# core.net
KiCad netlist of a schematic drawn in Altium Designer
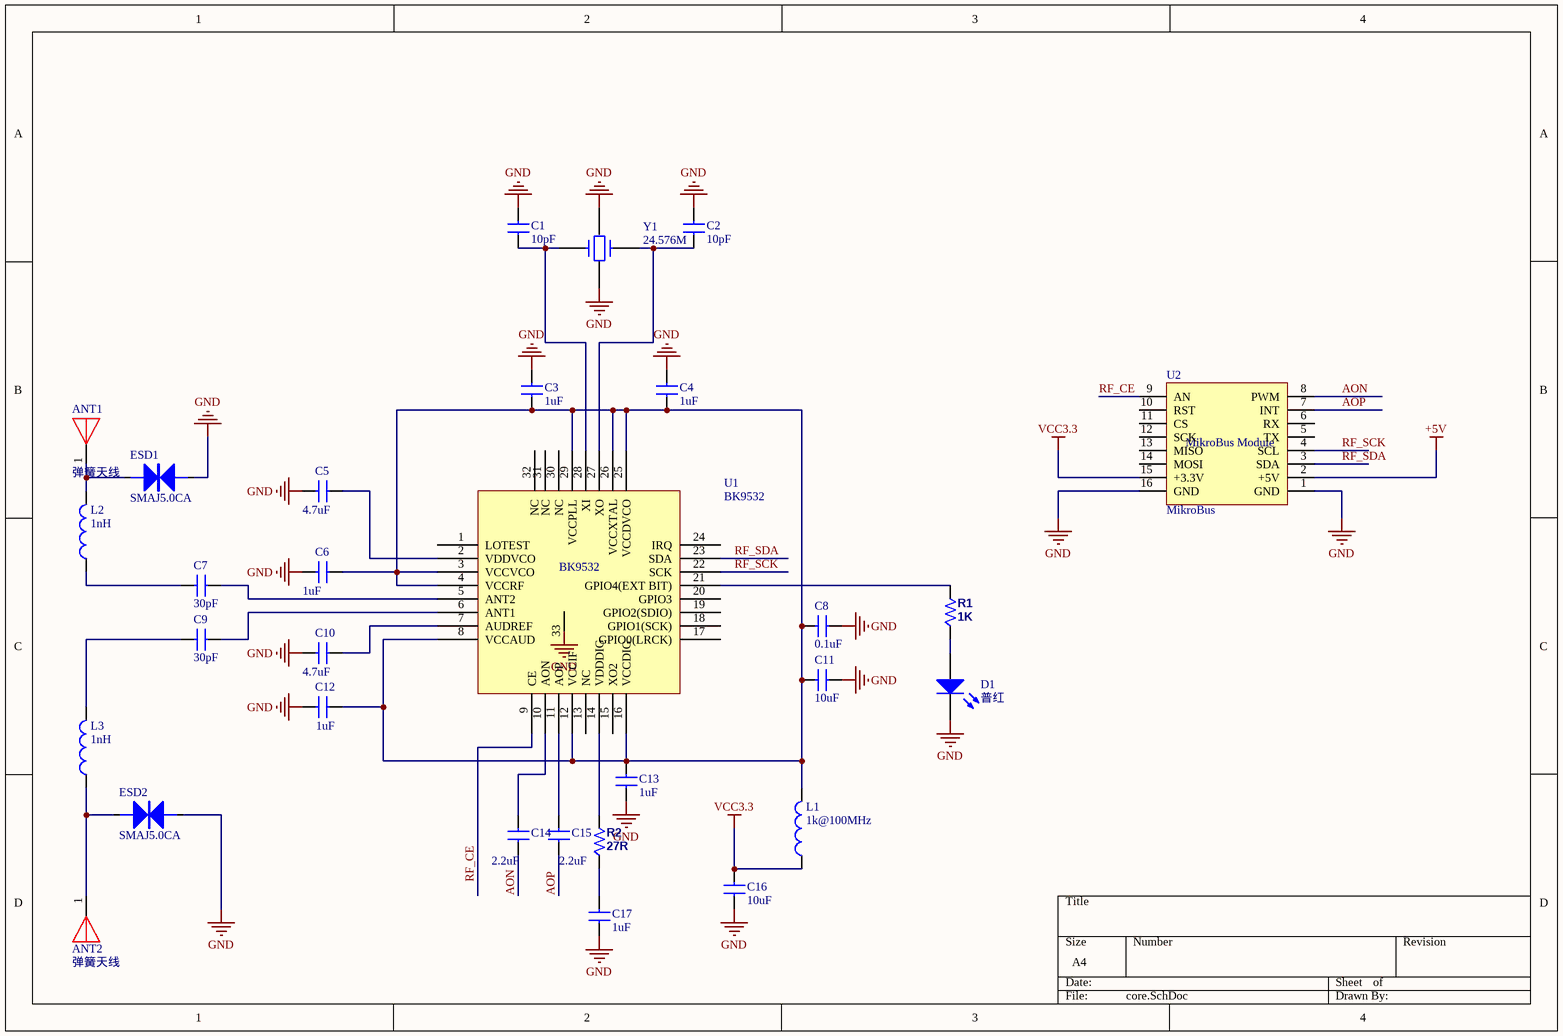
[diagram p0: core.SchDoc]

(export (version "E")
  (design (tool "Eeschema 10.0.6"))
  (components
    (comp (ref "ANT1")
      (value "弹簧天线")
      (footprint "ANT")
      (description "ANT")
      (libsource (lib "二极管") (part "ANT"))
    )
    (comp (ref "ANT2")
      (value "弹簧天线")
      (footprint "ANT")
      (description "ANT")
      (libsource (lib "二极管") (part "ANT"))
    )
    (comp (ref "C1")
      (value "10pF")
      (footprint "C0603")
      (description "0603-10pF/50V 贴片层叠电容")
      (libsource (lib "兰格封装") (part "CAP 0603-10pF/50V"))
    )
    (comp (ref "C2")
      (value "10pF")
      (footprint "C0603")
      (description "0603-10pF/50V 贴片层叠电容")
      (libsource (lib "兰格封装") (part "CAP 0603-10pF/50V"))
    )
    (comp (ref "C3")
      (value "1uF")
      (footprint "C0603")
      (description "0805-68pF/50V-J5%贴片层叠电容")
      (libsource (lib "兰格封装") (part "CAP 0805-68pF/50V"))
    )
    (comp (ref "C4")
      (value "1uF")
      (footprint "C0603")
      (description "0805-68pF/50V-J5%贴片层叠电容")
      (libsource (lib "兰格封装") (part "CAP 0805-68pF/50V"))
    )
    (comp (ref "C5")
      (value "4.7uF")
      (footprint "C0603")
      (description "0805-68pF/50V-J5%贴片层叠电容")
      (libsource (lib "兰格封装") (part "CAP 0805-68pF/50V"))
    )
    (comp (ref "C6")
      (value "1uF")
      (footprint "C0603")
      (description "0805-68pF/50V-J5%贴片层叠电容")
      (libsource (lib "兰格封装") (part "CAP 0805-68pF/50V"))
    )
    (comp (ref "C7")
      (value "30pF")
      (footprint "C0603")
      (description "0603-33pF/50V   贴片层叠电容")
      (libsource (lib "兰格封装") (part "CAP 0603-33pF/50V"))
    )
    (comp (ref "C8")
      (value "0.1uF")
      (footprint "C0603")
      (description "0805-68pF/50V-J5%贴片层叠电容")
      (libsource (lib "兰格封装") (part "CAP 0805-68pF/50V"))
    )
    (comp (ref "C9")
      (value "30pF")
      (footprint "C0603")
      (description "0603-33pF/50V   贴片层叠电容")
      (libsource (lib "兰格封装") (part "CAP 0603-33pF/50V"))
    )
    (comp (ref "C10")
      (value "4.7uF")
      (footprint "C0603")
      (description "0805-68pF/50V-J5%贴片层叠电容")
      (libsource (lib "兰格封装") (part "CAP 0805-68pF/50V"))
    )
    (comp (ref "C11")
      (value "10uF")
      (footprint "C0603")
      (description "0805-68pF/50V-J5%贴片层叠电容")
      (libsource (lib "兰格封装") (part "CAP 0805-68pF/50V"))
    )
    (comp (ref "C12")
      (value "1uF")
      (footprint "C0603")
      (description "0805-68pF/50V-J5%贴片层叠电容")
      (libsource (lib "兰格封装") (part "CAP 0805-68pF/50V"))
    )
    (comp (ref "C13")
      (value "1uF")
      (footprint "C0603")
      (description "0805-68pF/50V-J5%贴片层叠电容")
      (libsource (lib "兰格封装") (part "CAP 0805-68pF/50V"))
    )
    (comp (ref "C14")
      (value "2.2uF")
      (footprint "C0603")
      (description "0805-68pF/50V-J5%贴片层叠电容")
      (libsource (lib "兰格封装") (part "CAP 0805-68pF/50V"))
    )
    (comp (ref "C15")
      (value "2.2uF")
      (footprint "C0603")
      (description "0805-68pF/50V-J5%贴片层叠电容")
      (libsource (lib "兰格封装") (part "CAP 0805-68pF/50V"))
    )
    (comp (ref "C16")
      (value "10uF")
      (footprint "C0603")
      (description "0805-68pF/50V-J5%贴片层叠电容")
      (libsource (lib "兰格封装") (part "CAP 0805-68pF/50V"))
    )
    (comp (ref "C17")
      (value "1uF")
      (footprint "C0603")
      (description "0805-68pF/50V-J5%贴片层叠电容")
      (libsource (lib "兰格封装") (part "CAP 0805-68pF/50V"))
    )
    (comp (ref "D1")
      (value "普红")
      (footprint "LED 0805")
      (description "0805普亮贴片红灯")
      (libsource (lib "兰格封装") (part "LED  0805普亮贴片红灯"))
    )
    (comp (ref "ESD1")
      (value "SMAJ5.0CA")
      (footprint "SMAJ")
      (description "ESD 二极管")
      (libsource (lib "二极管") (part "ESD 防浪涌二极管"))
    )
    (comp (ref "ESD2")
      (value "SMAJ5.0CA")
      (footprint "SMAJ")
      (description "ESD 二极管")
      (libsource (lib "二极管") (part "ESD 防浪涌二极管"))
    )
    (comp (ref "L1")
      (value "1k@100MHz")
      (footprint "L0603")
      (description "磁珠")
      (libsource (lib "兰格封装") (part "电感  贴片  33UH"))
    )
    (comp (ref "L2")
      (value "1nH")
      (footprint "L0603")
      (description "0603 600R瓷珠电感")
      (libsource (lib "兰格封装") (part "电感  0603  600R"))
    )
    (comp (ref "L3")
      (value "1nH")
      (footprint "L0603")
      (description "0603 600R瓷珠电感")
      (libsource (lib "兰格封装") (part "电感  0603  600R"))
    )
    (comp (ref "R1")
      (value "1K")
      (footprint "R0603")
      (description "1206  K  5%  HS  贴片电阻")
      (libsource (lib "兰格封装") (part "RES1"))
    )
    (comp (ref "R2")
      (value "27R")
      (footprint "R0603")
      (description "1206  K  5%  HS  贴片电阻")
      (libsource (lib "兰格封装") (part "RES1"))
    )
    (comp (ref "U1")
      (value "BK9532")
      (footprint "QFN32")
      (description "QFN5x5 32")
      (libsource (lib "集成IC") (part "BK9532"))
    )
    (comp (ref "U2") (value "MikroBus") (footprint "MikroBus") (libsource (lib "集成IC") (part "MikroBus")))
    (comp (ref "Y1")
      (value "24.576M")
      (footprint "晶振   有源2520")
      (description "（未入库）24.576MHz  2520")
      (libsource (lib "晶体") (part "晶振  24.576MHz  49SMD"))
    )
  )
  (nets
    (net (code "1") (name "+5V") (class "Default")
      (node (ref "U2") (pin "2") (pinfunction "+5V_2") (pintype "passive"))
    )
    (net (code "2") (name "/AON") (class "Default")
      (node (ref "C14") (pin "1") (pinfunction "1_1") (pintype "passive"))
      (node (ref "U2") (pin "8") (pinfunction "PWM_8") (pintype "passive"))
    )
    (net (code "3") (name "/AOP") (class "Default")
      (node (ref "C15") (pin "1") (pinfunction "1_1") (pintype "passive"))
      (node (ref "U2") (pin "7") (pinfunction "INT_7") (pintype "passive"))
    )
    (net (code "4") (name "/RF_CE") (class "Default")
      (node (ref "U1") (pin "9") (pinfunction "CE_9") (pintype "passive"))
      (node (ref "U2") (pin "9") (pinfunction "AN_9") (pintype "passive"))
    )
    (net (code "5") (name "/RF_SCK") (class "Default")
      (node (ref "U1") (pin "22") (pinfunction "SCK_22") (pintype "passive"))
      (node (ref "U2") (pin "4") (pinfunction "SCL_4") (pintype "passive"))
    )
    (net (code "6") (name "/RF_SDA") (class "Default")
      (node (ref "U1") (pin "23") (pinfunction "SDA_23") (pintype "passive"))
      (node (ref "U2") (pin "3") (pinfunction "SDA_3") (pintype "passive"))
    )
    (net (code "7") (name "GND") (class "Default")
      (node (ref "C1") (pin "1") (pinfunction "1_1") (pintype "passive"))
      (node (ref "C10") (pin "1") (pinfunction "1_1") (pintype "passive"))
      (node (ref "C11") (pin "1") (pinfunction "1_1") (pintype "passive"))
      (node (ref "C12") (pin "1") (pinfunction "1_1") (pintype "passive"))
      (node (ref "C13") (pin "1") (pinfunction "1_1") (pintype "passive"))
      (node (ref "C16") (pin "1") (pinfunction "1_1") (pintype "passive"))
      (node (ref "C17") (pin "1") (pinfunction "1_1") (pintype "passive"))
      (node (ref "C2") (pin "1") (pinfunction "1_1") (pintype "passive"))
      (node (ref "C3") (pin "2") (pinfunction "2_2") (pintype "passive"))
      (node (ref "C4") (pin "2") (pinfunction "2_2") (pintype "passive"))
      (node (ref "C5") (pin "1") (pinfunction "1_1") (pintype "passive"))
      (node (ref "C6") (pin "1") (pinfunction "1_1") (pintype "passive"))
      (node (ref "C8") (pin "1") (pinfunction "1_1") (pintype "passive"))
      (node (ref "D1") (pin "2") (pinfunction "K_2") (pintype "passive"))
      (node (ref "ESD1") (pin "2") (pinfunction "2_2") (pintype "passive"))
      (node (ref "ESD2") (pin "1") (pinfunction "1_1") (pintype "passive"))
      (node (ref "U1") (pin "33") (pintype "passive"))
      (node (ref "U2") (pin "1") (pinfunction "GND_1") (pintype "passive"))
      (node (ref "U2") (pin "16") (pinfunction "GND_16") (pintype "passive"))
      (node (ref "Y1") (pin "2") (pinfunction "2_2") (pintype "passive"))
      (node (ref "Y1") (pin "4") (pinfunction "4_4") (pintype "passive"))
    )
    (net (code "8") (name "Net-(ANT1-Pad1)") (class "Default")
      (node (ref "ANT1") (pin "1") (pinfunction "1_1") (pintype "passive"))
      (node (ref "ESD1") (pin "1") (pinfunction "1_1") (pintype "passive"))
      (node (ref "L2") (pin "2") (pinfunction "2_2") (pintype "passive"))
    )
    (net (code "9") (name "Net-(ANT2-Pad1)") (class "Default")
      (node (ref "ANT2") (pin "1") (pinfunction "1_1") (pintype "passive"))
      (node (ref "ESD2") (pin "2") (pinfunction "2_2") (pintype "passive"))
      (node (ref "L3") (pin "1") (pinfunction "1_1") (pintype "passive"))
    )
    (net (code "10") (name "Net-(C7-Pad1)") (class "Default")
      (node (ref "C7") (pin "1") (pinfunction "1_1") (pintype "passive"))
      (node (ref "L2") (pin "1") (pinfunction "1_1") (pintype "passive"))
    )
    (net (code "11") (name "Net-(C9-Pad1)") (class "Default")
      (node (ref "C9") (pin "1") (pinfunction "1_1") (pintype "passive"))
      (node (ref "L3") (pin "2") (pinfunction "2_2") (pintype "passive"))
    )
    (net (code "12") (name "Net-(C17-Pad2)") (class "Default")
      (node (ref "C17") (pin "2") (pinfunction "2_2") (pintype "passive"))
      (node (ref "R2") (pin "1") (pintype "passive"))
    )
    (net (code "13") (name "Net-(D1-A)") (class "Default")
      (node (ref "D1") (pin "1") (pinfunction "A_1") (pintype "passive"))
      (node (ref "R1") (pin "1") (pintype "passive"))
    )
    (net (code "14") (name "Net-(U1-ANT1)") (class "Default")
      (node (ref "C9") (pin "2") (pinfunction "2_2") (pintype "passive"))
      (node (ref "U1") (pin "6") (pinfunction "ANT1_6") (pintype "passive"))
    )
    (net (code "15") (name "Net-(U1-ANT2)") (class "Default")
      (node (ref "C7") (pin "2") (pinfunction "2_2") (pintype "passive"))
      (node (ref "U1") (pin "5") (pinfunction "ANT2_5") (pintype "passive"))
    )
    (net (code "16") (name "Net-(U1-AON)") (class "Default")
      (node (ref "C14") (pin "2") (pinfunction "2_2") (pintype "passive"))
      (node (ref "U1") (pin "10") (pinfunction "AON_10") (pintype "passive"))
    )
    (net (code "17") (name "Net-(U1-AOP)") (class "Default")
      (node (ref "C15") (pin "2") (pinfunction "2_2") (pintype "passive"))
      (node (ref "U1") (pin "11") (pinfunction "AOP_11") (pintype "passive"))
    )
    (net (code "18") (name "Net-(U1-AUDREF)") (class "Default")
      (node (ref "C10") (pin "2") (pinfunction "2_2") (pintype "passive"))
      (node (ref "U1") (pin "7") (pinfunction "AUDREF_7") (pintype "passive"))
    )
    (net (code "19") (name "Net-(U1-GPIO4(EXT_BIT))") (class "Default")
      (node (ref "R1") (pin "2") (pintype "passive"))
      (node (ref "U1") (pin "21") (pinfunction "GPIO4(EXT_BIT)_21") (pintype "passive"))
    )
    (net (code "20") (name "Net-(U1-VCCAUD)") (class "Default")
      (node (ref "C11") (pin "2") (pinfunction "2_2") (pintype "passive"))
      (node (ref "C12") (pin "2") (pinfunction "2_2") (pintype "passive"))
      (node (ref "C13") (pin "2") (pinfunction "2_2") (pintype "passive"))
      (node (ref "C3") (pin "1") (pinfunction "1_1") (pintype "passive"))
      (node (ref "C4") (pin "1") (pinfunction "1_1") (pintype "passive"))
      (node (ref "C6") (pin "2") (pinfunction "2_2") (pintype "passive"))
      (node (ref "C8") (pin "2") (pinfunction "2_2") (pintype "passive"))
      (node (ref "L1") (pin "2") (pinfunction "2_2") (pintype "passive"))
      (node (ref "U1") (pin "12") (pinfunction "VCCIF_12") (pintype "passive"))
      (node (ref "U1") (pin "16") (pinfunction "VCCDIG_16") (pintype "passive"))
      (node (ref "U1") (pin "25") (pinfunction "VCCDVCO_25") (pintype "passive"))
      (node (ref "U1") (pin "26") (pinfunction "VCCXTAL_26") (pintype "passive"))
      (node (ref "U1") (pin "29") (pinfunction "VCCPLL_29") (pintype "passive"))
      (node (ref "U1") (pin "3") (pinfunction "VCCVCO_3") (pintype "passive"))
      (node (ref "U1") (pin "4") (pinfunction "VCCRF_4") (pintype "passive"))
      (node (ref "U1") (pin "8") (pinfunction "VCCAUD_8") (pintype "passive"))
    )
    (net (code "21") (name "Net-(U1-VDDDIG)") (class "Default")
      (node (ref "R2") (pin "2") (pintype "passive"))
      (node (ref "U1") (pin "14") (pinfunction "VDDDIG_14") (pintype "passive"))
    )
    (net (code "22") (name "Net-(U1-VDDVCO)") (class "Default")
      (node (ref "C5") (pin "2") (pinfunction "2_2") (pintype "passive"))
      (node (ref "U1") (pin "2") (pinfunction "VDDVCO_2") (pintype "passive"))
    )
    (net (code "23") (name "Net-(U1-XI)") (class "Default")
      (node (ref "C1") (pin "2") (pinfunction "2_2") (pintype "passive"))
      (node (ref "U1") (pin "28") (pinfunction "XI_28") (pintype "passive"))
      (node (ref "Y1") (pin "1") (pinfunction "1_1") (pintype "passive"))
    )
    (net (code "24") (name "Net-(U1-XO)") (class "Default")
      (node (ref "C2") (pin "2") (pinfunction "2_2") (pintype "passive"))
      (node (ref "U1") (pin "27") (pinfunction "XO_27") (pintype "passive"))
      (node (ref "Y1") (pin "3") (pinfunction "3_3") (pintype "passive"))
    )
    (net (code "25") (name "VCC3.3") (class "Default")
      (node (ref "C16") (pin "2") (pinfunction "2_2") (pintype "passive"))
      (node (ref "L1") (pin "1") (pinfunction "1_1") (pintype "passive"))
      (node (ref "U2") (pin "15") (pinfunction "+3.3V_15") (pintype "passive"))
    )
    (net (code "26") (name "unconnected-(U1-GPIO0(LRCK)-Pad17)") (class "Default")
      (node (ref "U1") (pin "17") (pinfunction "GPIO0(LRCK)_17") (pintype "passive"))
    )
    (net (code "27") (name "unconnected-(U1-GPIO1(SCK)-Pad18)") (class "Default")
      (node (ref "U1") (pin "18") (pinfunction "GPIO1(SCK)_18") (pintype "passive"))
    )
    (net (code "28") (name "unconnected-(U1-GPIO2(SDIO)-Pad19)") (class "Default")
      (node (ref "U1") (pin "19") (pinfunction "GPIO2(SDIO)_19") (pintype "passive"))
    )
    (net (code "29") (name "unconnected-(U1-GPIO3-Pad20)") (class "Default")
      (node (ref "U1") (pin "20") (pinfunction "GPIO3_20") (pintype "passive"))
    )
    (net (code "30") (name "unconnected-(U1-IRQ-Pad24)") (class "Default")
      (node (ref "U1") (pin "24") (pinfunction "IRQ_24") (pintype "passive"))
    )
    (net (code "31") (name "unconnected-(U1-LOTEST-Pad1)") (class "Default")
      (node (ref "U1") (pin "1") (pinfunction "LOTEST_1") (pintype "passive"))
    )
    (net (code "32") (name "unconnected-(U1-NC-Pad13)") (class "Default")
      (node (ref "U1") (pin "13") (pinfunction "NC_13") (pintype "passive"))
    )
    (net (code "33") (name "unconnected-(U1-NC-Pad30)") (class "Default")
      (node (ref "U1") (pin "30") (pinfunction "NC_30") (pintype "passive"))
    )
    (net (code "34") (name "unconnected-(U1-NC-Pad31)") (class "Default")
      (node (ref "U1") (pin "31") (pinfunction "NC_31") (pintype "passive"))
    )
    (net (code "35") (name "unconnected-(U1-NC-Pad32)") (class "Default")
      (node (ref "U1") (pin "32") (pinfunction "NC_32") (pintype "passive"))
    )
    (net (code "36") (name "unconnected-(U1-XO2-Pad15)") (class "Default")
      (node (ref "U1") (pin "15") (pinfunction "XO2_15") (pintype "passive"))
    )
    (net (code "37") (name "unconnected-(U2-CS-Pad11)") (class "Default")
      (node (ref "U2") (pin "11") (pinfunction "CS_11") (pintype "passive"))
    )
    (net (code "38") (name "unconnected-(U2-MISO-Pad13)") (class "Default")
      (node (ref "U2") (pin "13") (pinfunction "MISO_13") (pintype "passive"))
    )
    (net (code "39") (name "unconnected-(U2-MOSI-Pad14)") (class "Default")
      (node (ref "U2") (pin "14") (pinfunction "MOSI_14") (pintype "passive"))
    )
    (net (code "40") (name "unconnected-(U2-RST-Pad10)") (class "Default")
      (node (ref "U2") (pin "10") (pinfunction "RST_10") (pintype "passive"))
    )
    (net (code "41") (name "unconnected-(U2-RX-Pad6)") (class "Default")
      (node (ref "U2") (pin "6") (pinfunction "RX_6") (pintype "passive"))
    )
    (net (code "42") (name "unconnected-(U2-SCK-Pad12)") (class "Default")
      (node (ref "U2") (pin "12") (pinfunction "SCK_12") (pintype "passive"))
    )
    (net (code "43") (name "unconnected-(U2-TX-Pad5)") (class "Default")
      (node (ref "U2") (pin "5") (pinfunction "TX_5") (pintype "passive"))
    )
  )
)
